# cherrymx1.net
KiCad netlist of a schematic drawn in EAGLE
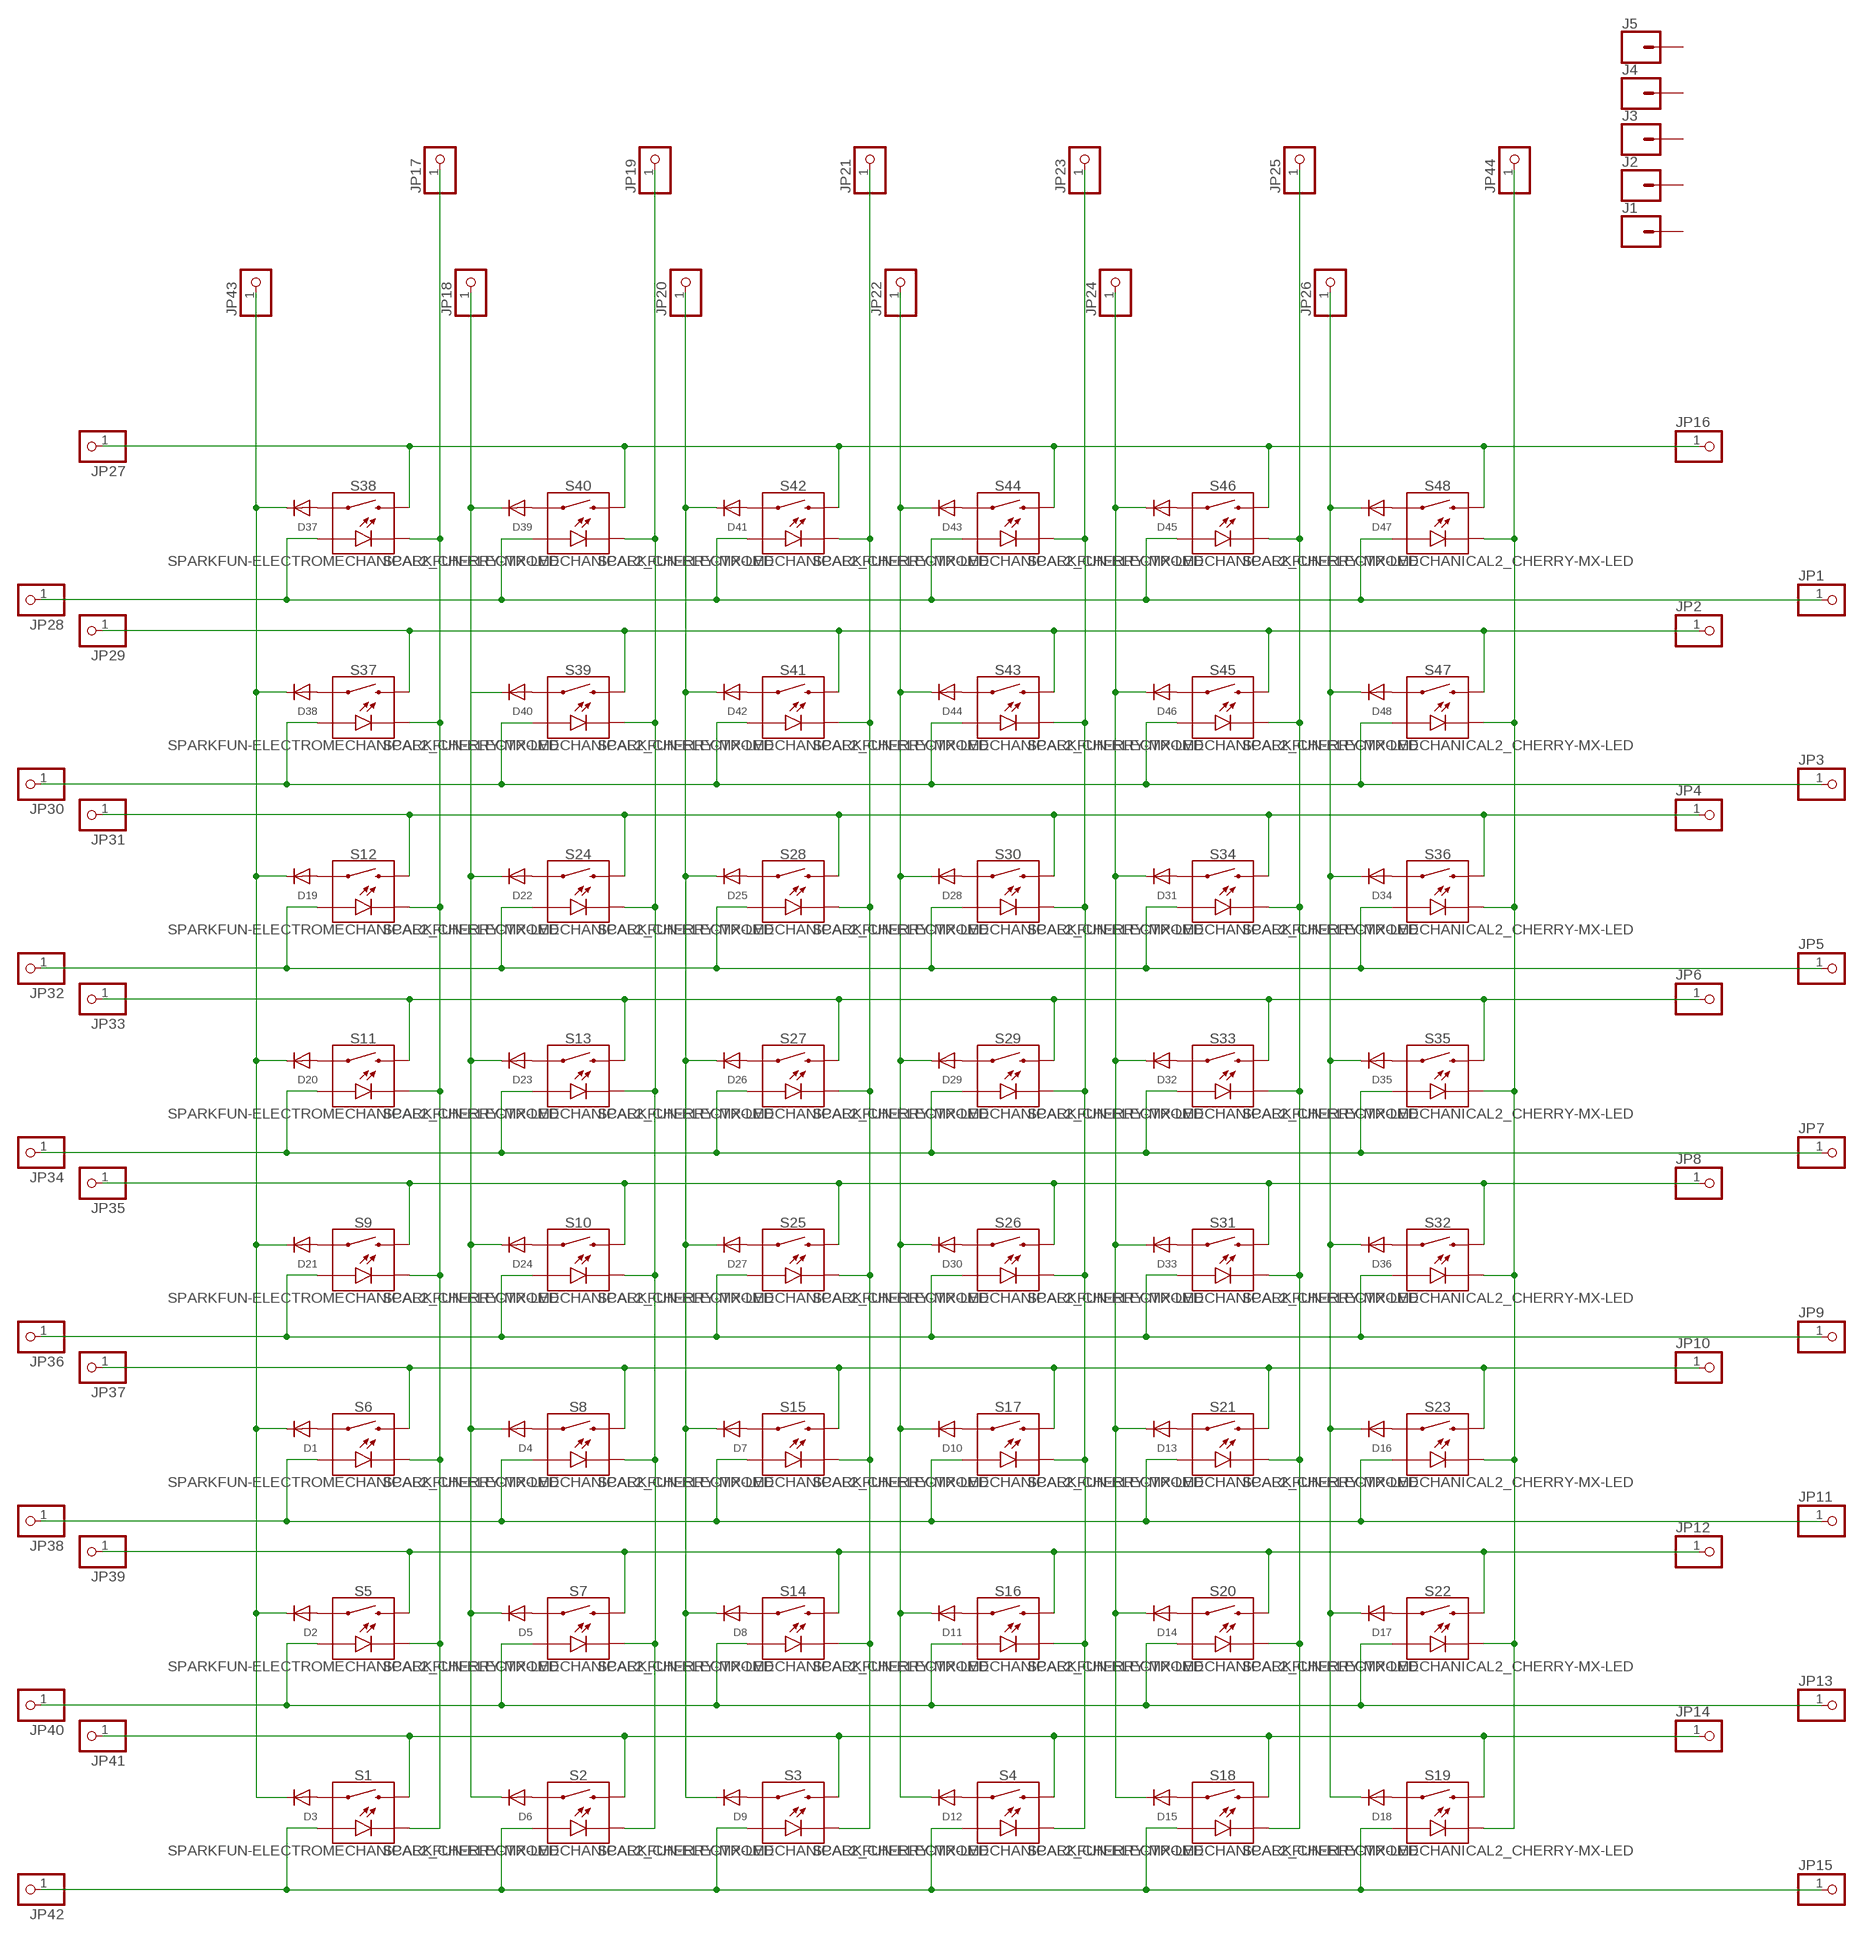
[diagram p0: schematic, sheet 1]

(export (version "E")
  (design (tool "Eeschema 10.0.6"))
  (components
    (comp (ref "D1")
      (value "DIODE_SOD-123FL")
      (footprint "eagle-import:SOD-123FL")
      (libsource (lib "eagle-import") (part "DIODE_SOD-123FL"))
    )
    (comp (ref "D2")
      (value "DIODE_SOD-123FL")
      (footprint "eagle-import:SOD-123FL")
      (libsource (lib "eagle-import") (part "DIODE_SOD-123FL"))
    )
    (comp (ref "D3")
      (value "DIODE_SOD-123FL")
      (footprint "eagle-import:SOD-123FL")
      (libsource (lib "eagle-import") (part "DIODE_SOD-123FL"))
    )
    (comp (ref "D4")
      (value "DIODE_SOD-123FL")
      (footprint "eagle-import:SOD-123FL")
      (libsource (lib "eagle-import") (part "DIODE_SOD-123FL"))
    )
    (comp (ref "D5")
      (value "DIODE_SOD-123FL")
      (footprint "eagle-import:SOD-123FL")
      (libsource (lib "eagle-import") (part "DIODE_SOD-123FL"))
    )
    (comp (ref "D6")
      (value "DIODE_SOD-123FL")
      (footprint "eagle-import:SOD-123FL")
      (libsource (lib "eagle-import") (part "DIODE_SOD-123FL"))
    )
    (comp (ref "D7")
      (value "DIODE_SOD-123FL")
      (footprint "eagle-import:SOD-123FL")
      (libsource (lib "eagle-import") (part "DIODE_SOD-123FL"))
    )
    (comp (ref "D8")
      (value "DIODE_SOD-123FL")
      (footprint "eagle-import:SOD-123FL")
      (libsource (lib "eagle-import") (part "DIODE_SOD-123FL"))
    )
    (comp (ref "D9")
      (value "DIODE_SOD-123FL")
      (footprint "eagle-import:SOD-123FL")
      (libsource (lib "eagle-import") (part "DIODE_SOD-123FL"))
    )
    (comp (ref "D10")
      (value "DIODE_SOD-123FL")
      (footprint "eagle-import:SOD-123FL")
      (libsource (lib "eagle-import") (part "DIODE_SOD-123FL"))
    )
    (comp (ref "D11")
      (value "DIODE_SOD-123FL")
      (footprint "eagle-import:SOD-123FL")
      (libsource (lib "eagle-import") (part "DIODE_SOD-123FL"))
    )
    (comp (ref "D12")
      (value "DIODE_SOD-123FL")
      (footprint "eagle-import:SOD-123FL")
      (libsource (lib "eagle-import") (part "DIODE_SOD-123FL"))
    )
    (comp (ref "D13")
      (value "DIODE_SOD-123FL")
      (footprint "eagle-import:SOD-123FL")
      (libsource (lib "eagle-import") (part "DIODE_SOD-123FL"))
    )
    (comp (ref "D14")
      (value "DIODE_SOD-123FL")
      (footprint "eagle-import:SOD-123FL")
      (libsource (lib "eagle-import") (part "DIODE_SOD-123FL"))
    )
    (comp (ref "D15")
      (value "DIODE_SOD-123FL")
      (footprint "eagle-import:SOD-123FL")
      (libsource (lib "eagle-import") (part "DIODE_SOD-123FL"))
    )
    (comp (ref "D16")
      (value "DIODE_SOD-123FL")
      (footprint "eagle-import:SOD-123FL")
      (libsource (lib "eagle-import") (part "DIODE_SOD-123FL"))
    )
    (comp (ref "D17")
      (value "DIODE_SOD-123FL")
      (footprint "eagle-import:SOD-123FL")
      (libsource (lib "eagle-import") (part "DIODE_SOD-123FL"))
    )
    (comp (ref "D18")
      (value "DIODE_SOD-123FL")
      (footprint "eagle-import:SOD-123FL")
      (libsource (lib "eagle-import") (part "DIODE_SOD-123FL"))
    )
    (comp (ref "D19")
      (value "DIODE_SOD-123FL")
      (footprint "eagle-import:SOD-123FL")
      (libsource (lib "eagle-import") (part "DIODE_SOD-123FL"))
    )
    (comp (ref "D20")
      (value "DIODE_SOD-123FL")
      (footprint "eagle-import:SOD-123FL")
      (libsource (lib "eagle-import") (part "DIODE_SOD-123FL"))
    )
    (comp (ref "D21")
      (value "DIODE_SOD-123FL")
      (footprint "eagle-import:SOD-123FL")
      (libsource (lib "eagle-import") (part "DIODE_SOD-123FL"))
    )
    (comp (ref "D22")
      (value "DIODE_SOD-123FL")
      (footprint "eagle-import:SOD-123FL")
      (libsource (lib "eagle-import") (part "DIODE_SOD-123FL"))
    )
    (comp (ref "D23")
      (value "DIODE_SOD-123FL")
      (footprint "eagle-import:SOD-123FL")
      (libsource (lib "eagle-import") (part "DIODE_SOD-123FL"))
    )
    (comp (ref "D24")
      (value "DIODE_SOD-123FL")
      (footprint "eagle-import:SOD-123FL")
      (libsource (lib "eagle-import") (part "DIODE_SOD-123FL"))
    )
    (comp (ref "D25")
      (value "DIODE_SOD-123FL")
      (footprint "eagle-import:SOD-123FL")
      (libsource (lib "eagle-import") (part "DIODE_SOD-123FL"))
    )
    (comp (ref "D26")
      (value "DIODE_SOD-123FL")
      (footprint "eagle-import:SOD-123FL")
      (libsource (lib "eagle-import") (part "DIODE_SOD-123FL"))
    )
    (comp (ref "D27")
      (value "DIODE_SOD-123FL")
      (footprint "eagle-import:SOD-123FL")
      (libsource (lib "eagle-import") (part "DIODE_SOD-123FL"))
    )
    (comp (ref "D28")
      (value "DIODE_SOD-123FL")
      (footprint "eagle-import:SOD-123FL")
      (libsource (lib "eagle-import") (part "DIODE_SOD-123FL"))
    )
    (comp (ref "D29")
      (value "DIODE_SOD-123FL")
      (footprint "eagle-import:SOD-123FL")
      (libsource (lib "eagle-import") (part "DIODE_SOD-123FL"))
    )
    (comp (ref "D30")
      (value "DIODE_SOD-123FL")
      (footprint "eagle-import:SOD-123FL")
      (libsource (lib "eagle-import") (part "DIODE_SOD-123FL"))
    )
    (comp (ref "D31")
      (value "DIODE_SOD-123FL")
      (footprint "eagle-import:SOD-123FL")
      (libsource (lib "eagle-import") (part "DIODE_SOD-123FL"))
    )
    (comp (ref "D32")
      (value "DIODE_SOD-123FL")
      (footprint "eagle-import:SOD-123FL")
      (libsource (lib "eagle-import") (part "DIODE_SOD-123FL"))
    )
    (comp (ref "D33")
      (value "DIODE_SOD-123FL")
      (footprint "eagle-import:SOD-123FL")
      (libsource (lib "eagle-import") (part "DIODE_SOD-123FL"))
    )
    (comp (ref "D34")
      (value "DIODE_SOD-123FL")
      (footprint "eagle-import:SOD-123FL")
      (libsource (lib "eagle-import") (part "DIODE_SOD-123FL"))
    )
    (comp (ref "D35")
      (value "DIODE_SOD-123FL")
      (footprint "eagle-import:SOD-123FL")
      (libsource (lib "eagle-import") (part "DIODE_SOD-123FL"))
    )
    (comp (ref "D36")
      (value "DIODE_SOD-123FL")
      (footprint "eagle-import:SOD-123FL")
      (libsource (lib "eagle-import") (part "DIODE_SOD-123FL"))
    )
    (comp (ref "D37")
      (value "DIODE_SOD-123FL")
      (footprint "eagle-import:SOD-123FL")
      (libsource (lib "eagle-import") (part "DIODE_SOD-123FL"))
    )
    (comp (ref "D38")
      (value "DIODE_SOD-123FL")
      (footprint "eagle-import:SOD-123FL")
      (libsource (lib "eagle-import") (part "DIODE_SOD-123FL"))
    )
    (comp (ref "D39")
      (value "DIODE_SOD-123FL")
      (footprint "eagle-import:SOD-123FL")
      (libsource (lib "eagle-import") (part "DIODE_SOD-123FL"))
    )
    (comp (ref "D40")
      (value "DIODE_SOD-123FL")
      (footprint "eagle-import:SOD-123FL")
      (libsource (lib "eagle-import") (part "DIODE_SOD-123FL"))
    )
    (comp (ref "D41")
      (value "DIODE_SOD-123FL")
      (footprint "eagle-import:SOD-123FL")
      (libsource (lib "eagle-import") (part "DIODE_SOD-123FL"))
    )
    (comp (ref "D42")
      (value "DIODE_SOD-123FL")
      (footprint "eagle-import:SOD-123FL")
      (libsource (lib "eagle-import") (part "DIODE_SOD-123FL"))
    )
    (comp (ref "D43")
      (value "DIODE_SOD-123FL")
      (footprint "eagle-import:SOD-123FL")
      (libsource (lib "eagle-import") (part "DIODE_SOD-123FL"))
    )
    (comp (ref "D44")
      (value "DIODE_SOD-123FL")
      (footprint "eagle-import:SOD-123FL")
      (libsource (lib "eagle-import") (part "DIODE_SOD-123FL"))
    )
    (comp (ref "D45")
      (value "DIODE_SOD-123FL")
      (footprint "eagle-import:SOD-123FL")
      (libsource (lib "eagle-import") (part "DIODE_SOD-123FL"))
    )
    (comp (ref "D46")
      (value "DIODE_SOD-123FL")
      (footprint "eagle-import:SOD-123FL")
      (libsource (lib "eagle-import") (part "DIODE_SOD-123FL"))
    )
    (comp (ref "D47")
      (value "DIODE_SOD-123FL")
      (footprint "eagle-import:SOD-123FL")
      (libsource (lib "eagle-import") (part "DIODE_SOD-123FL"))
    )
    (comp (ref "D48")
      (value "DIODE_SOD-123FL")
      (footprint "eagle-import:SOD-123FL")
      (libsource (lib "eagle-import") (part "DIODE_SOD-123FL"))
    )
    (comp (ref "J1")
      (value "CONN_01SMTSO-256-ET-0.165DIA")
      (footprint "eagle-import:SMTSO-256-ET-0.165DIA")
      (libsource (lib "eagle-import") (part "CONN_01SMTSO-256-ET-0.165DIA"))
    )
    (comp (ref "J2")
      (value "CONN_01SMTSO-256-ET-0.165DIA")
      (footprint "eagle-import:SMTSO-256-ET-0.165DIA")
      (libsource (lib "eagle-import") (part "CONN_01SMTSO-256-ET-0.165DIA"))
    )
    (comp (ref "J3")
      (value "CONN_01SMTSO-256-ET-0.165DIA")
      (footprint "eagle-import:SMTSO-256-ET-0.165DIA")
      (libsource (lib "eagle-import") (part "CONN_01SMTSO-256-ET-0.165DIA"))
    )
    (comp (ref "J4")
      (value "CONN_01SMTSO-256-ET-0.165DIA")
      (footprint "eagle-import:SMTSO-256-ET-0.165DIA")
      (libsource (lib "eagle-import") (part "CONN_01SMTSO-256-ET-0.165DIA"))
    )
    (comp (ref "J5")
      (value "CONN_01SMTSO-256-ET-0.165DIA")
      (footprint "eagle-import:SMTSO-256-ET-0.165DIA")
      (libsource (lib "eagle-import") (part "CONN_01SMTSO-256-ET-0.165DIA"))
    )
    (comp (ref "JP1")
      (value "MICROBUILDER_HEADER-1X51X1_EDGESMT")
      (footprint "eagle-import:MICROBUILDER_1X5_SMT")
      (libsource (lib "eagle-import") (part "MICROBUILDER_HEADER-1X51X1_EDGESMT"))
    )
    (comp (ref "JP2")
      (value "MICROBUILDER_HEADER-1X51X1_EDGESMT")
      (footprint "eagle-import:MICROBUILDER_1X5_SMT")
      (libsource (lib "eagle-import") (part "MICROBUILDER_HEADER-1X51X1_EDGESMT"))
    )
    (comp (ref "JP3")
      (value "MICROBUILDER_HEADER-1X51X1_EDGESMT")
      (footprint "eagle-import:MICROBUILDER_1X5_SMT")
      (libsource (lib "eagle-import") (part "MICROBUILDER_HEADER-1X51X1_EDGESMT"))
    )
    (comp (ref "JP4")
      (value "MICROBUILDER_HEADER-1X51X1_EDGESMT")
      (footprint "eagle-import:MICROBUILDER_1X5_SMT")
      (libsource (lib "eagle-import") (part "MICROBUILDER_HEADER-1X51X1_EDGESMT"))
    )
    (comp (ref "JP5")
      (value "MICROBUILDER_HEADER-1X51X1_EDGESMT")
      (footprint "eagle-import:MICROBUILDER_1X5_SMT")
      (libsource (lib "eagle-import") (part "MICROBUILDER_HEADER-1X51X1_EDGESMT"))
    )
    (comp (ref "JP6")
      (value "MICROBUILDER_HEADER-1X51X1_EDGESMT")
      (footprint "eagle-import:MICROBUILDER_1X5_SMT")
      (libsource (lib "eagle-import") (part "MICROBUILDER_HEADER-1X51X1_EDGESMT"))
    )
    (comp (ref "JP7")
      (value "MICROBUILDER_HEADER-1X51X1_EDGESMT")
      (footprint "eagle-import:MICROBUILDER_1X5_SMT")
      (libsource (lib "eagle-import") (part "MICROBUILDER_HEADER-1X51X1_EDGESMT"))
    )
    (comp (ref "JP8")
      (value "MICROBUILDER_HEADER-1X51X1_EDGESMT")
      (footprint "eagle-import:MICROBUILDER_1X5_SMT")
      (libsource (lib "eagle-import") (part "MICROBUILDER_HEADER-1X51X1_EDGESMT"))
    )
    (comp (ref "JP9")
      (value "MICROBUILDER_HEADER-1X51X1_EDGESMT")
      (footprint "eagle-import:MICROBUILDER_1X5_SMT")
      (libsource (lib "eagle-import") (part "MICROBUILDER_HEADER-1X51X1_EDGESMT"))
    )
    (comp (ref "JP10")
      (value "MICROBUILDER_HEADER-1X51X1_EDGESMT")
      (footprint "eagle-import:MICROBUILDER_1X5_SMT")
      (libsource (lib "eagle-import") (part "MICROBUILDER_HEADER-1X51X1_EDGESMT"))
    )
    (comp (ref "JP11")
      (value "MICROBUILDER_HEADER-1X51X1_EDGESMT")
      (footprint "eagle-import:MICROBUILDER_1X5_SMT")
      (libsource (lib "eagle-import") (part "MICROBUILDER_HEADER-1X51X1_EDGESMT"))
    )
    (comp (ref "JP12")
      (value "MICROBUILDER_HEADER-1X51X1_EDGESMT")
      (footprint "eagle-import:MICROBUILDER_1X5_SMT")
      (libsource (lib "eagle-import") (part "MICROBUILDER_HEADER-1X51X1_EDGESMT"))
    )
    (comp (ref "JP13")
      (value "MICROBUILDER_HEADER-1X51X1_EDGESMT")
      (footprint "eagle-import:MICROBUILDER_1X5_SMT")
      (libsource (lib "eagle-import") (part "MICROBUILDER_HEADER-1X51X1_EDGESMT"))
    )
    (comp (ref "JP14")
      (value "MICROBUILDER_HEADER-1X51X1_EDGESMT")
      (footprint "eagle-import:MICROBUILDER_1X5_SMT")
      (libsource (lib "eagle-import") (part "MICROBUILDER_HEADER-1X51X1_EDGESMT"))
    )
    (comp (ref "JP15")
      (value "MICROBUILDER_HEADER-1X51X1_EDGESMT")
      (footprint "eagle-import:MICROBUILDER_1X5_SMT")
      (libsource (lib "eagle-import") (part "MICROBUILDER_HEADER-1X51X1_EDGESMT"))
    )
    (comp (ref "JP16")
      (value "MICROBUILDER_HEADER-1X51X1_EDGESMT")
      (footprint "eagle-import:MICROBUILDER_1X5_SMT")
      (libsource (lib "eagle-import") (part "MICROBUILDER_HEADER-1X51X1_EDGESMT"))
    )
    (comp (ref "JP17")
      (value "MICROBUILDER_HEADER-1X51X1_EDGESMT")
      (footprint "eagle-import:MICROBUILDER_1X5_SMT")
      (libsource (lib "eagle-import") (part "MICROBUILDER_HEADER-1X51X1_EDGESMT"))
    )
    (comp (ref "JP18")
      (value "MICROBUILDER_HEADER-1X51X1_EDGESMT")
      (footprint "eagle-import:MICROBUILDER_1X5_SMT")
      (libsource (lib "eagle-import") (part "MICROBUILDER_HEADER-1X51X1_EDGESMT"))
    )
    (comp (ref "JP19")
      (value "MICROBUILDER_HEADER-1X51X1_EDGESMT")
      (footprint "eagle-import:MICROBUILDER_1X5_SMT")
      (libsource (lib "eagle-import") (part "MICROBUILDER_HEADER-1X51X1_EDGESMT"))
    )
    (comp (ref "JP20")
      (value "MICROBUILDER_HEADER-1X51X1_EDGESMT")
      (footprint "eagle-import:MICROBUILDER_1X5_SMT")
      (libsource (lib "eagle-import") (part "MICROBUILDER_HEADER-1X51X1_EDGESMT"))
    )
    (comp (ref "JP21")
      (value "MICROBUILDER_HEADER-1X51X1_EDGESMT")
      (footprint "eagle-import:MICROBUILDER_1X5_SMT")
      (libsource (lib "eagle-import") (part "MICROBUILDER_HEADER-1X51X1_EDGESMT"))
    )
    (comp (ref "JP22")
      (value "MICROBUILDER_HEADER-1X51X1_EDGESMT")
      (footprint "eagle-import:MICROBUILDER_1X5_SMT")
      (libsource (lib "eagle-import") (part "MICROBUILDER_HEADER-1X51X1_EDGESMT"))
    )
    (comp (ref "JP23")
      (value "MICROBUILDER_HEADER-1X51X1_EDGESMT")
      (footprint "eagle-import:MICROBUILDER_1X5_SMT")
      (libsource (lib "eagle-import") (part "MICROBUILDER_HEADER-1X51X1_EDGESMT"))
    )
    (comp (ref "JP24")
      (value "MICROBUILDER_HEADER-1X51X1_EDGESMT")
      (footprint "eagle-import:MICROBUILDER_1X5_SMT")
      (libsource (lib "eagle-import") (part "MICROBUILDER_HEADER-1X51X1_EDGESMT"))
    )
    (comp (ref "JP25")
      (value "MICROBUILDER_HEADER-1X51X1_EDGESMT")
      (footprint "eagle-import:MICROBUILDER_1X5_SMT")
      (libsource (lib "eagle-import") (part "MICROBUILDER_HEADER-1X51X1_EDGESMT"))
    )
    (comp (ref "JP26")
      (value "MICROBUILDER_HEADER-1X51X1_EDGESMT")
      (footprint "eagle-import:MICROBUILDER_1X5_SMT")
      (libsource (lib "eagle-import") (part "MICROBUILDER_HEADER-1X51X1_EDGESMT"))
    )
    (comp (ref "JP27")
      (value "MICROBUILDER_HEADER-1X51X1_EDGESMT")
      (footprint "eagle-import:MICROBUILDER_1X5_SMT")
      (libsource (lib "eagle-import") (part "MICROBUILDER_HEADER-1X51X1_EDGESMT"))
    )
    (comp (ref "JP28")
      (value "MICROBUILDER_HEADER-1X51X1_EDGESMT")
      (footprint "eagle-import:MICROBUILDER_1X5_SMT")
      (libsource (lib "eagle-import") (part "MICROBUILDER_HEADER-1X51X1_EDGESMT"))
    )
    (comp (ref "JP29")
      (value "MICROBUILDER_HEADER-1X51X1_EDGESMT")
      (footprint "eagle-import:MICROBUILDER_1X5_SMT")
      (libsource (lib "eagle-import") (part "MICROBUILDER_HEADER-1X51X1_EDGESMT"))
    )
    (comp (ref "JP30")
      (value "MICROBUILDER_HEADER-1X51X1_EDGESMT")
      (footprint "eagle-import:MICROBUILDER_1X5_SMT")
      (libsource (lib "eagle-import") (part "MICROBUILDER_HEADER-1X51X1_EDGESMT"))
    )
    (comp (ref "JP31")
      (value "MICROBUILDER_HEADER-1X51X1_EDGESMT")
      (footprint "eagle-import:MICROBUILDER_1X5_SMT")
      (libsource (lib "eagle-import") (part "MICROBUILDER_HEADER-1X51X1_EDGESMT"))
    )
    (comp (ref "JP32")
      (value "MICROBUILDER_HEADER-1X51X1_EDGESMT")
      (footprint "eagle-import:MICROBUILDER_1X5_SMT")
      (libsource (lib "eagle-import") (part "MICROBUILDER_HEADER-1X51X1_EDGESMT"))
    )
    (comp (ref "JP33")
      (value "MICROBUILDER_HEADER-1X51X1_EDGESMT")
      (footprint "eagle-import:MICROBUILDER_1X5_SMT")
      (libsource (lib "eagle-import") (part "MICROBUILDER_HEADER-1X51X1_EDGESMT"))
    )
    (comp (ref "JP34")
      (value "MICROBUILDER_HEADER-1X51X1_EDGESMT")
      (footprint "eagle-import:MICROBUILDER_1X5_SMT")
      (libsource (lib "eagle-import") (part "MICROBUILDER_HEADER-1X51X1_EDGESMT"))
    )
    (comp (ref "JP35")
      (value "MICROBUILDER_HEADER-1X51X1_EDGESMT")
      (footprint "eagle-import:MICROBUILDER_1X5_SMT")
      (libsource (lib "eagle-import") (part "MICROBUILDER_HEADER-1X51X1_EDGESMT"))
    )
    (comp (ref "JP36")
      (value "MICROBUILDER_HEADER-1X51X1_EDGESMT")
      (footprint "eagle-import:MICROBUILDER_1X5_SMT")
      (libsource (lib "eagle-import") (part "MICROBUILDER_HEADER-1X51X1_EDGESMT"))
    )
    (comp (ref "JP37")
      (value "MICROBUILDER_HEADER-1X51X1_EDGESMT")
      (footprint "eagle-import:MICROBUILDER_1X5_SMT")
      (libsource (lib "eagle-import") (part "MICROBUILDER_HEADER-1X51X1_EDGESMT"))
    )
    (comp (ref "JP38")
      (value "MICROBUILDER_HEADER-1X51X1_EDGESMT")
      (footprint "eagle-import:MICROBUILDER_1X5_SMT")
      (libsource (lib "eagle-import") (part "MICROBUILDER_HEADER-1X51X1_EDGESMT"))
    )
    (comp (ref "JP39")
      (value "MICROBUILDER_HEADER-1X51X1_EDGESMT")
      (footprint "eagle-import:MICROBUILDER_1X5_SMT")
      (libsource (lib "eagle-import") (part "MICROBUILDER_HEADER-1X51X1_EDGESMT"))
    )
    (comp (ref "JP40")
      (value "MICROBUILDER_HEADER-1X51X1_EDGESMT")
      (footprint "eagle-import:MICROBUILDER_1X5_SMT")
      (libsource (lib "eagle-import") (part "MICROBUILDER_HEADER-1X51X1_EDGESMT"))
    )
    (comp (ref "JP41")
      (value "MICROBUILDER_HEADER-1X51X1_EDGESMT")
      (footprint "eagle-import:MICROBUILDER_1X5_SMT")
      (libsource (lib "eagle-import") (part "MICROBUILDER_HEADER-1X51X1_EDGESMT"))
    )
    (comp (ref "JP42")
      (value "MICROBUILDER_HEADER-1X51X1_EDGESMT")
      (footprint "eagle-import:MICROBUILDER_1X5_SMT")
      (libsource (lib "eagle-import") (part "MICROBUILDER_HEADER-1X51X1_EDGESMT"))
    )
    (comp (ref "JP43")
      (value "MICROBUILDER_HEADER-1X51X1_EDGESMT")
      (footprint "eagle-import:MICROBUILDER_1X5_SMT")
      (libsource (lib "eagle-import") (part "MICROBUILDER_HEADER-1X51X1_EDGESMT"))
    )
    (comp (ref "JP44")
      (value "MICROBUILDER_HEADER-1X51X1_EDGESMT")
      (footprint "eagle-import:MICROBUILDER_1X5_SMT")
      (libsource (lib "eagle-import") (part "MICROBUILDER_HEADER-1X51X1_EDGESMT"))
    )
    (comp (ref "S1")
      (value "SPARKFUN-ELECTROMECHANICAL2_CHERRY-MX-LED")
      (footprint "eagle-import:SPARKFUN-ELECTROMECHANICAL2_CHERRY-MX-LED")
      (libsource (lib "eagle-import") (part "SPARKFUN-ELECTROMECHANICAL2_CHERRY-MX-LED"))
    )
    (comp (ref "S2")
      (value "SPARKFUN-ELECTROMECHANICAL2_CHERRY-MX-LED")
      (footprint "eagle-import:SPARKFUN-ELECTROMECHANICAL2_CHERRY-MX-LED")
      (libsource (lib "eagle-import") (part "SPARKFUN-ELECTROMECHANICAL2_CHERRY-MX-LED"))
    )
    (comp (ref "S3")
      (value "SPARKFUN-ELECTROMECHANICAL2_CHERRY-MX-LED")
      (footprint "eagle-import:SPARKFUN-ELECTROMECHANICAL2_CHERRY-MX-LED")
      (libsource (lib "eagle-import") (part "SPARKFUN-ELECTROMECHANICAL2_CHERRY-MX-LED"))
    )
    (comp (ref "S4")
      (value "SPARKFUN-ELECTROMECHANICAL2_CHERRY-MX-LED")
      (footprint "eagle-import:SPARKFUN-ELECTROMECHANICAL2_CHERRY-MX-LED")
      (libsource (lib "eagle-import") (part "SPARKFUN-ELECTROMECHANICAL2_CHERRY-MX-LED"))
    )
    (comp (ref "S5")
      (value "SPARKFUN-ELECTROMECHANICAL2_CHERRY-MX-LED")
      (footprint "eagle-import:SPARKFUN-ELECTROMECHANICAL2_CHERRY-MX-LED")
      (libsource (lib "eagle-import") (part "SPARKFUN-ELECTROMECHANICAL2_CHERRY-MX-LED"))
    )
    (comp (ref "S6")
      (value "SPARKFUN-ELECTROMECHANICAL2_CHERRY-MX-LED")
      (footprint "eagle-import:SPARKFUN-ELECTROMECHANICAL2_CHERRY-MX-LED")
      (libsource (lib "eagle-import") (part "SPARKFUN-ELECTROMECHANICAL2_CHERRY-MX-LED"))
    )
    (comp (ref "S7")
      (value "SPARKFUN-ELECTROMECHANICAL2_CHERRY-MX-LED")
      (footprint "eagle-import:SPARKFUN-ELECTROMECHANICAL2_CHERRY-MX-LED")
      (libsource (lib "eagle-import") (part "SPARKFUN-ELECTROMECHANICAL2_CHERRY-MX-LED"))
    )
    (comp (ref "S8")
      (value "SPARKFUN-ELECTROMECHANICAL2_CHERRY-MX-LED")
      (footprint "eagle-import:SPARKFUN-ELECTROMECHANICAL2_CHERRY-MX-LED")
      (libsource (lib "eagle-import") (part "SPARKFUN-ELECTROMECHANICAL2_CHERRY-MX-LED"))
    )
    (comp (ref "S9")
      (value "SPARKFUN-ELECTROMECHANICAL2_CHERRY-MX-LED")
      (footprint "eagle-import:SPARKFUN-ELECTROMECHANICAL2_CHERRY-MX-LED")
      (libsource (lib "eagle-import") (part "SPARKFUN-ELECTROMECHANICAL2_CHERRY-MX-LED"))
    )
    (comp (ref "S10")
      (value "SPARKFUN-ELECTROMECHANICAL2_CHERRY-MX-LED")
      (footprint "eagle-import:SPARKFUN-ELECTROMECHANICAL2_CHERRY-MX-LED")
      (libsource (lib "eagle-import") (part "SPARKFUN-ELECTROMECHANICAL2_CHERRY-MX-LED"))
    )
    (comp (ref "S11")
      (value "SPARKFUN-ELECTROMECHANICAL2_CHERRY-MX-LED")
      (footprint "eagle-import:SPARKFUN-ELECTROMECHANICAL2_CHERRY-MX-LED")
      (libsource (lib "eagle-import") (part "SPARKFUN-ELECTROMECHANICAL2_CHERRY-MX-LED"))
    )
    (comp (ref "S12")
      (value "SPARKFUN-ELECTROMECHANICAL2_CHERRY-MX-LED")
      (footprint "eagle-import:SPARKFUN-ELECTROMECHANICAL2_CHERRY-MX-LED")
      (libsource (lib "eagle-import") (part "SPARKFUN-ELECTROMECHANICAL2_CHERRY-MX-LED"))
    )
    (comp (ref "S13")
      (value "SPARKFUN-ELECTROMECHANICAL2_CHERRY-MX-LED")
      (footprint "eagle-import:SPARKFUN-ELECTROMECHANICAL2_CHERRY-MX-LED")
      (libsource (lib "eagle-import") (part "SPARKFUN-ELECTROMECHANICAL2_CHERRY-MX-LED"))
    )
    (comp (ref "S14")
      (value "SPARKFUN-ELECTROMECHANICAL2_CHERRY-MX-LED")
      (footprint "eagle-import:SPARKFUN-ELECTROMECHANICAL2_CHERRY-MX-LED")
      (libsource (lib "eagle-import") (part "SPARKFUN-ELECTROMECHANICAL2_CHERRY-MX-LED"))
    )
    (comp (ref "S15")
      (value "SPARKFUN-ELECTROMECHANICAL2_CHERRY-MX-LED")
      (footprint "eagle-import:SPARKFUN-ELECTROMECHANICAL2_CHERRY-MX-LED")
      (libsource (lib "eagle-import") (part "SPARKFUN-ELECTROMECHANICAL2_CHERRY-MX-LED"))
    )
    (comp (ref "S16")
      (value "SPARKFUN-ELECTROMECHANICAL2_CHERRY-MX-LED")
      (footprint "eagle-import:SPARKFUN-ELECTROMECHANICAL2_CHERRY-MX-LED")
      (libsource (lib "eagle-import") (part "SPARKFUN-ELECTROMECHANICAL2_CHERRY-MX-LED"))
    )
    (comp (ref "S17")
      (value "SPARKFUN-ELECTROMECHANICAL2_CHERRY-MX-LED")
      (footprint "eagle-import:SPARKFUN-ELECTROMECHANICAL2_CHERRY-MX-LED")
      (libsource (lib "eagle-import") (part "SPARKFUN-ELECTROMECHANICAL2_CHERRY-MX-LED"))
    )
    (comp (ref "S18")
      (value "SPARKFUN-ELECTROMECHANICAL2_CHERRY-MX-LED")
      (footprint "eagle-import:SPARKFUN-ELECTROMECHANICAL2_CHERRY-MX-LED")
      (libsource (lib "eagle-import") (part "SPARKFUN-ELECTROMECHANICAL2_CHERRY-MX-LED"))
    )
    (comp (ref "S19")
      (value "SPARKFUN-ELECTROMECHANICAL2_CHERRY-MX-LED")
      (footprint "eagle-import:SPARKFUN-ELECTROMECHANICAL2_CHERRY-MX-LED")
      (libsource (lib "eagle-import") (part "SPARKFUN-ELECTROMECHANICAL2_CHERRY-MX-LED"))
    )
    (comp (ref "S20")
      (value "SPARKFUN-ELECTROMECHANICAL2_CHERRY-MX-LED")
      (footprint "eagle-import:SPARKFUN-ELECTROMECHANICAL2_CHERRY-MX-LED")
      (libsource (lib "eagle-import") (part "SPARKFUN-ELECTROMECHANICAL2_CHERRY-MX-LED"))
    )
    (comp (ref "S21")
      (value "SPARKFUN-ELECTROMECHANICAL2_CHERRY-MX-LED")
      (footprint "eagle-import:SPARKFUN-ELECTROMECHANICAL2_CHERRY-MX-LED")
      (libsource (lib "eagle-import") (part "SPARKFUN-ELECTROMECHANICAL2_CHERRY-MX-LED"))
    )
    (comp (ref "S22")
      (value "SPARKFUN-ELECTROMECHANICAL2_CHERRY-MX-LED")
      (footprint "eagle-import:SPARKFUN-ELECTROMECHANICAL2_CHERRY-MX-LED")
      (libsource (lib "eagle-import") (part "SPARKFUN-ELECTROMECHANICAL2_CHERRY-MX-LED"))
    )
    (comp (ref "S23")
      (value "SPARKFUN-ELECTROMECHANICAL2_CHERRY-MX-LED")
      (footprint "eagle-import:SPARKFUN-ELECTROMECHANICAL2_CHERRY-MX-LED")
      (libsource (lib "eagle-import") (part "SPARKFUN-ELECTROMECHANICAL2_CHERRY-MX-LED"))
    )
    (comp (ref "S24")
      (value "SPARKFUN-ELECTROMECHANICAL2_CHERRY-MX-LED")
      (footprint "eagle-import:SPARKFUN-ELECTROMECHANICAL2_CHERRY-MX-LED")
      (libsource (lib "eagle-import") (part "SPARKFUN-ELECTROMECHANICAL2_CHERRY-MX-LED"))
    )
    (comp (ref "S25")
      (value "SPARKFUN-ELECTROMECHANICAL2_CHERRY-MX-LED")
      (footprint "eagle-import:SPARKFUN-ELECTROMECHANICAL2_CHERRY-MX-LED")
      (libsource (lib "eagle-import") (part "SPARKFUN-ELECTROMECHANICAL2_CHERRY-MX-LED"))
    )
    (comp (ref "S26")
      (value "SPARKFUN-ELECTROMECHANICAL2_CHERRY-MX-LED")
      (footprint "eagle-import:SPARKFUN-ELECTROMECHANICAL2_CHERRY-MX-LED")
      (libsource (lib "eagle-import") (part "SPARKFUN-ELECTROMECHANICAL2_CHERRY-MX-LED"))
    )
    (comp (ref "S27")
      (value "SPARKFUN-ELECTROMECHANICAL2_CHERRY-MX-LED")
      (footprint "eagle-import:SPARKFUN-ELECTROMECHANICAL2_CHERRY-MX-LED")
      (libsource (lib "eagle-import") (part "SPARKFUN-ELECTROMECHANICAL2_CHERRY-MX-LED"))
    )
    (comp (ref "S28")
      (value "SPARKFUN-ELECTROMECHANICAL2_CHERRY-MX-LED")
      (footprint "eagle-import:SPARKFUN-ELECTROMECHANICAL2_CHERRY-MX-LED")
      (libsource (lib "eagle-import") (part "SPARKFUN-ELECTROMECHANICAL2_CHERRY-MX-LED"))
    )
    (comp (ref "S29")
      (value "SPARKFUN-ELECTROMECHANICAL2_CHERRY-MX-LED")
      (footprint "eagle-import:SPARKFUN-ELECTROMECHANICAL2_CHERRY-MX-LED")
      (libsource (lib "eagle-import") (part "SPARKFUN-ELECTROMECHANICAL2_CHERRY-MX-LED"))
    )
    (comp (ref "S30")
      (value "SPARKFUN-ELECTROMECHANICAL2_CHERRY-MX-LED")
      (footprint "eagle-import:SPARKFUN-ELECTROMECHANICAL2_CHERRY-MX-LED")
      (libsource (lib "eagle-import") (part "SPARKFUN-ELECTROMECHANICAL2_CHERRY-MX-LED"))
    )
    (comp (ref "S31")
      (value "SPARKFUN-ELECTROMECHANICAL2_CHERRY-MX-LED")
      (footprint "eagle-import:SPARKFUN-ELECTROMECHANICAL2_CHERRY-MX-LED")
      (libsource (lib "eagle-import") (part "SPARKFUN-ELECTROMECHANICAL2_CHERRY-MX-LED"))
    )
    (comp (ref "S32")
      (value "SPARKFUN-ELECTROMECHANICAL2_CHERRY-MX-LED")
      (footprint "eagle-import:SPARKFUN-ELECTROMECHANICAL2_CHERRY-MX-LED")
      (libsource (lib "eagle-import") (part "SPARKFUN-ELECTROMECHANICAL2_CHERRY-MX-LED"))
    )
    (comp (ref "S33")
      (value "SPARKFUN-ELECTROMECHANICAL2_CHERRY-MX-LED")
      (footprint "eagle-import:SPARKFUN-ELECTROMECHANICAL2_CHERRY-MX-LED")
      (libsource (lib "eagle-import") (part "SPARKFUN-ELECTROMECHANICAL2_CHERRY-MX-LED"))
    )
    (comp (ref "S34")
      (value "SPARKFUN-ELECTROMECHANICAL2_CHERRY-MX-LED")
      (footprint "eagle-import:SPARKFUN-ELECTROMECHANICAL2_CHERRY-MX-LED")
      (libsource (lib "eagle-import") (part "SPARKFUN-ELECTROMECHANICAL2_CHERRY-MX-LED"))
    )
    (comp (ref "S35")
      (value "SPARKFUN-ELECTROMECHANICAL2_CHERRY-MX-LED")
      (footprint "eagle-import:SPARKFUN-ELECTROMECHANICAL2_CHERRY-MX-LED")
      (libsource (lib "eagle-import") (part "SPARKFUN-ELECTROMECHANICAL2_CHERRY-MX-LED"))
    )
    (comp (ref "S36")
      (value "SPARKFUN-ELECTROMECHANICAL2_CHERRY-MX-LED")
      (footprint "eagle-import:SPARKFUN-ELECTROMECHANICAL2_CHERRY-MX-LED")
      (libsource (lib "eagle-import") (part "SPARKFUN-ELECTROMECHANICAL2_CHERRY-MX-LED"))
    )
    (comp (ref "S37")
      (value "SPARKFUN-ELECTROMECHANICAL2_CHERRY-MX-LED")
      (footprint "eagle-import:SPARKFUN-ELECTROMECHANICAL2_CHERRY-MX-LED")
      (libsource (lib "eagle-import") (part "SPARKFUN-ELECTROMECHANICAL2_CHERRY-MX-LED"))
    )
    (comp (ref "S38")
      (value "SPARKFUN-ELECTROMECHANICAL2_CHERRY-MX-LED")
      (footprint "eagle-import:SPARKFUN-ELECTROMECHANICAL2_CHERRY-MX-LED")
      (libsource (lib "eagle-import") (part "SPARKFUN-ELECTROMECHANICAL2_CHERRY-MX-LED"))
    )
    (comp (ref "S39")
      (value "SPARKFUN-ELECTROMECHANICAL2_CHERRY-MX-LED")
      (footprint "eagle-import:SPARKFUN-ELECTROMECHANICAL2_CHERRY-MX-LED")
      (libsource (lib "eagle-import") (part "SPARKFUN-ELECTROMECHANICAL2_CHERRY-MX-LED"))
    )
    (comp (ref "S40")
      (value "SPARKFUN-ELECTROMECHANICAL2_CHERRY-MX-LED")
      (footprint "eagle-import:SPARKFUN-ELECTROMECHANICAL2_CHERRY-MX-LED")
      (libsource (lib "eagle-import") (part "SPARKFUN-ELECTROMECHANICAL2_CHERRY-MX-LED"))
    )
    (comp (ref "S41")
      (value "SPARKFUN-ELECTROMECHANICAL2_CHERRY-MX-LED")
      (footprint "eagle-import:SPARKFUN-ELECTROMECHANICAL2_CHERRY-MX-LED")
      (libsource (lib "eagle-import") (part "SPARKFUN-ELECTROMECHANICAL2_CHERRY-MX-LED"))
    )
    (comp (ref "S42")
      (value "SPARKFUN-ELECTROMECHANICAL2_CHERRY-MX-LED")
      (footprint "eagle-import:SPARKFUN-ELECTROMECHANICAL2_CHERRY-MX-LED")
      (libsource (lib "eagle-import") (part "SPARKFUN-ELECTROMECHANICAL2_CHERRY-MX-LED"))
    )
    (comp (ref "S43")
      (value "SPARKFUN-ELECTROMECHANICAL2_CHERRY-MX-LED")
      (footprint "eagle-import:SPARKFUN-ELECTROMECHANICAL2_CHERRY-MX-LED")
      (libsource (lib "eagle-import") (part "SPARKFUN-ELECTROMECHANICAL2_CHERRY-MX-LED"))
    )
    (comp (ref "S44")
      (value "SPARKFUN-ELECTROMECHANICAL2_CHERRY-MX-LED")
      (footprint "eagle-import:SPARKFUN-ELECTROMECHANICAL2_CHERRY-MX-LED")
      (libsource (lib "eagle-import") (part "SPARKFUN-ELECTROMECHANICAL2_CHERRY-MX-LED"))
    )
    (comp (ref "S45")
      (value "SPARKFUN-ELECTROMECHANICAL2_CHERRY-MX-LED")
      (footprint "eagle-import:SPARKFUN-ELECTROMECHANICAL2_CHERRY-MX-LED")
      (libsource (lib "eagle-import") (part "SPARKFUN-ELECTROMECHANICAL2_CHERRY-MX-LED"))
    )
    (comp (ref "S46")
      (value "SPARKFUN-ELECTROMECHANICAL2_CHERRY-MX-LED")
      (footprint "eagle-import:SPARKFUN-ELECTROMECHANICAL2_CHERRY-MX-LED")
      (libsource (lib "eagle-import") (part "SPARKFUN-ELECTROMECHANICAL2_CHERRY-MX-LED"))
    )
    (comp (ref "S47")
      (value "SPARKFUN-ELECTROMECHANICAL2_CHERRY-MX-LED")
      (footprint "eagle-import:SPARKFUN-ELECTROMECHANICAL2_CHERRY-MX-LED")
      (libsource (lib "eagle-import") (part "SPARKFUN-ELECTROMECHANICAL2_CHERRY-MX-LED"))
    )
    (comp (ref "S48")
      (value "SPARKFUN-ELECTROMECHANICAL2_CHERRY-MX-LED")
      (footprint "eagle-import:SPARKFUN-ELECTROMECHANICAL2_CHERRY-MX-LED")
      (libsource (lib "eagle-import") (part "SPARKFUN-ELECTROMECHANICAL2_CHERRY-MX-LED"))
    )
  )
  (nets
    (net (code "1") (name "Net-(D1-PadA)") (class "Default")
      (node (ref "D1") (pin "A") (pinfunction "A_A") (pintype "passive"))
      (node (ref "S6") (pin "S1") (pinfunction "S1_S1") (pintype "passive"))
    )
    (net (code "2") (name "Net-(D1-PadC)") (class "Default")
      (node (ref "D1") (pin "C") (pinfunction "C_C") (pintype "passive"))
      (node (ref "D19") (pin "C") (pinfunction "C_C") (pintype "passive"))
      (node (ref "D2") (pin "C") (pinfunction "C_C") (pintype "passive"))
      (node (ref "D20") (pin "C") (pinfunction "C_C") (pintype "passive"))
      (node (ref "D21") (pin "C") (pinfunction "C_C") (pintype "passive"))
      (node (ref "D3") (pin "C") (pinfunction "C_C") (pintype "passive"))
      (node (ref "D37") (pin "C") (pinfunction "C_C") (pintype "passive"))
      (node (ref "D38") (pin "C") (pinfunction "C_C") (pintype "passive"))
      (node (ref "JP43") (pin "1") (pinfunction "1_1") (pintype "passive"))
    )
    (net (code "3") (name "Net-(D2-PadA)") (class "Default")
      (node (ref "D2") (pin "A") (pinfunction "A_A") (pintype "passive"))
      (node (ref "S5") (pin "S1") (pinfunction "S1_S1") (pintype "passive"))
    )
    (net (code "4") (name "Net-(D3-PadA)") (class "Default")
      (node (ref "D3") (pin "A") (pinfunction "A_A") (pintype "passive"))
      (node (ref "S1") (pin "S1") (pinfunction "S1_S1") (pintype "passive"))
    )
    (net (code "5") (name "Net-(D4-PadA)") (class "Default")
      (node (ref "D4") (pin "A") (pinfunction "A_A") (pintype "passive"))
      (node (ref "S8") (pin "S1") (pinfunction "S1_S1") (pintype "passive"))
    )
    (net (code "6") (name "Net-(D5-PadA)") (class "Default")
      (node (ref "D5") (pin "A") (pinfunction "A_A") (pintype "passive"))
      (node (ref "S7") (pin "S1") (pinfunction "S1_S1") (pintype "passive"))
    )
    (net (code "7") (name "Net-(D6-PadA)") (class "Default")
      (node (ref "D6") (pin "A") (pinfunction "A_A") (pintype "passive"))
      (node (ref "S2") (pin "S1") (pinfunction "S1_S1") (pintype "passive"))
    )
    (net (code "8") (name "Net-(D7-PadA)") (class "Default")
      (node (ref "D7") (pin "A") (pinfunction "A_A") (pintype "passive"))
      (node (ref "S15") (pin "S1") (pinfunction "S1_S1") (pintype "passive"))
    )
    (net (code "9") (name "Net-(D8-PadA)") (class "Default")
      (node (ref "D8") (pin "A") (pinfunction "A_A") (pintype "passive"))
      (node (ref "S14") (pin "S1") (pinfunction "S1_S1") (pintype "passive"))
    )
    (net (code "10") (name "Net-(D9-PadA)") (class "Default")
      (node (ref "D9") (pin "A") (pinfunction "A_A") (pintype "passive"))
      (node (ref "S3") (pin "S1") (pinfunction "S1_S1") (pintype "passive"))
    )
    (net (code "11") (name "Net-(D10-PadA)") (class "Default")
      (node (ref "D10") (pin "A") (pinfunction "A_A") (pintype "passive"))
      (node (ref "S17") (pin "S1") (pinfunction "S1_S1") (pintype "passive"))
    )
    (net (code "12") (name "Net-(D10-PadC)") (class "Default")
      (node (ref "D10") (pin "C") (pinfunction "C_C") (pintype "passive"))
      (node (ref "D11") (pin "C") (pinfunction "C_C") (pintype "passive"))
      (node (ref "D12") (pin "C") (pinfunction "C_C") (pintype "passive"))
      (node (ref "D28") (pin "C") (pinfunction "C_C") (pintype "passive"))
      (node (ref "D29") (pin "C") (pinfunction "C_C") (pintype "passive"))
      (node (ref "D30") (pin "C") (pinfunction "C_C") (pintype "passive"))
      (node (ref "D43") (pin "C") (pinfunction "C_C") (pintype "passive"))
      (node (ref "D44") (pin "C") (pinfunction "C_C") (pintype "passive"))
      (node (ref "JP22") (pin "1") (pinfunction "1_1") (pintype "passive"))
    )
    (net (code "13") (name "Net-(D11-PadA)") (class "Default")
      (node (ref "D11") (pin "A") (pinfunction "A_A") (pintype "passive"))
      (node (ref "S16") (pin "S1") (pinfunction "S1_S1") (pintype "passive"))
    )
    (net (code "14") (name "Net-(D12-PadA)") (class "Default")
      (node (ref "D12") (pin "A") (pinfunction "A_A") (pintype "passive"))
      (node (ref "S4") (pin "S1") (pinfunction "S1_S1") (pintype "passive"))
    )
    (net (code "15") (name "Net-(D13-PadA)") (class "Default")
      (node (ref "D13") (pin "A") (pinfunction "A_A") (pintype "passive"))
      (node (ref "S21") (pin "S1") (pinfunction "S1_S1") (pintype "passive"))
    )
    (net (code "16") (name "Net-(D13-PadC)") (class "Default")
      (node (ref "D13") (pin "C") (pinfunction "C_C") (pintype "passive"))
      (node (ref "D14") (pin "C") (pinfunction "C_C") (pintype "passive"))
      (node (ref "D15") (pin "C") (pinfunction "C_C") (pintype "passive"))
      (node (ref "D31") (pin "C") (pinfunction "C_C") (pintype "passive"))
      (node (ref "D32") (pin "C") (pinfunction "C_C") (pintype "passive"))
      (node (ref "D33") (pin "C") (pinfunction "C_C") (pintype "passive"))
      (node (ref "D45") (pin "C") (pinfunction "C_C") (pintype "passive"))
      (node (ref "D46") (pin "C") (pinfunction "C_C") (pintype "passive"))
      (node (ref "JP24") (pin "1") (pinfunction "1_1") (pintype "passive"))
    )
    (net (code "17") (name "Net-(D14-PadA)") (class "Default")
      (node (ref "D14") (pin "A") (pinfunction "A_A") (pintype "passive"))
      (node (ref "S20") (pin "S1") (pinfunction "S1_S1") (pintype "passive"))
    )
    (net (code "18") (name "Net-(D15-PadA)") (class "Default")
      (node (ref "D15") (pin "A") (pinfunction "A_A") (pintype "passive"))
      (node (ref "S18") (pin "S1") (pinfunction "S1_S1") (pintype "passive"))
    )
    (net (code "19") (name "Net-(D16-PadA)") (class "Default")
      (node (ref "D16") (pin "A") (pinfunction "A_A") (pintype "passive"))
      (node (ref "S23") (pin "S1") (pinfunction "S1_S1") (pintype "passive"))
    )
    (net (code "20") (name "Net-(D16-PadC)") (class "Default")
      (node (ref "D16") (pin "C") (pinfunction "C_C") (pintype "passive"))
      (node (ref "D17") (pin "C") (pinfunction "C_C") (pintype "passive"))
      (node (ref "D18") (pin "C") (pinfunction "C_C") (pintype "passive"))
      (node (ref "D34") (pin "C") (pinfunction "C_C") (pintype "passive"))
      (node (ref "D35") (pin "C") (pinfunction "C_C") (pintype "passive"))
      (node (ref "D36") (pin "C") (pinfunction "C_C") (pintype "passive"))
      (node (ref "D47") (pin "C") (pinfunction "C_C") (pintype "passive"))
      (node (ref "D48") (pin "C") (pinfunction "C_C") (pintype "passive"))
      (node (ref "JP26") (pin "1") (pinfunction "1_1") (pintype "passive"))
    )
    (net (code "21") (name "Net-(D17-PadA)") (class "Default")
      (node (ref "D17") (pin "A") (pinfunction "A_A") (pintype "passive"))
      (node (ref "S22") (pin "S1") (pinfunction "S1_S1") (pintype "passive"))
    )
    (net (code "22") (name "Net-(D18-PadA)") (class "Default")
      (node (ref "D18") (pin "A") (pinfunction "A_A") (pintype "passive"))
      (node (ref "S19") (pin "S1") (pinfunction "S1_S1") (pintype "passive"))
    )
    (net (code "23") (name "Net-(D19-PadA)") (class "Default")
      (node (ref "D19") (pin "A") (pinfunction "A_A") (pintype "passive"))
      (node (ref "S12") (pin "S1") (pinfunction "S1_S1") (pintype "passive"))
    )
    (net (code "24") (name "Net-(D20-PadA)") (class "Default")
      (node (ref "D20") (pin "A") (pinfunction "A_A") (pintype "passive"))
      (node (ref "S11") (pin "S1") (pinfunction "S1_S1") (pintype "passive"))
    )
    (net (code "25") (name "Net-(D21-PadA)") (class "Default")
      (node (ref "D21") (pin "A") (pinfunction "A_A") (pintype "passive"))
      (node (ref "S9") (pin "S1") (pinfunction "S1_S1") (pintype "passive"))
    )
    (net (code "26") (name "Net-(D22-PadA)") (class "Default")
      (node (ref "D22") (pin "A") (pinfunction "A_A") (pintype "passive"))
      (node (ref "S24") (pin "S1") (pinfunction "S1_S1") (pintype "passive"))
    )
    (net (code "27") (name "Net-(D22-PadC)") (class "Default")
      (node (ref "D22") (pin "C") (pinfunction "C_C") (pintype "passive"))
      (node (ref "D23") (pin "C") (pinfunction "C_C") (pintype "passive"))
      (node (ref "D24") (pin "C") (pinfunction "C_C") (pintype "passive"))
      (node (ref "D39") (pin "C") (pinfunction "C_C") (pintype "passive"))
      (node (ref "D4") (pin "C") (pinfunction "C_C") (pintype "passive"))
      (node (ref "D40") (pin "C") (pinfunction "C_C") (pintype "passive"))
      (node (ref "D5") (pin "C") (pinfunction "C_C") (pintype "passive"))
      (node (ref "D6") (pin "C") (pinfunction "C_C") (pintype "passive"))
      (node (ref "JP18") (pin "1") (pinfunction "1_1") (pintype "passive"))
    )
    (net (code "28") (name "Net-(D23-PadA)") (class "Default")
      (node (ref "D23") (pin "A") (pinfunction "A_A") (pintype "passive"))
      (node (ref "S13") (pin "S1") (pinfunction "S1_S1") (pintype "passive"))
    )
    (net (code "29") (name "Net-(D24-PadA)") (class "Default")
      (node (ref "D24") (pin "A") (pinfunction "A_A") (pintype "passive"))
      (node (ref "S10") (pin "S1") (pinfunction "S1_S1") (pintype "passive"))
    )
    (net (code "30") (name "Net-(D25-PadA)") (class "Default")
      (node (ref "D25") (pin "A") (pinfunction "A_A") (pintype "passive"))
      (node (ref "S28") (pin "S1") (pinfunction "S1_S1") (pintype "passive"))
    )
    (net (code "31") (name "Net-(D25-PadC)") (class "Default")
      (node (ref "D25") (pin "C") (pinfunction "C_C") (pintype "passive"))
      (node (ref "D26") (pin "C") (pinfunction "C_C") (pintype "passive"))
      (node (ref "D27") (pin "C") (pinfunction "C_C") (pintype "passive"))
      (node (ref "D41") (pin "C") (pinfunction "C_C") (pintype "passive"))
      (node (ref "D42") (pin "C") (pinfunction "C_C") (pintype "passive"))
      (node (ref "D7") (pin "C") (pinfunction "C_C") (pintype "passive"))
      (node (ref "D8") (pin "C") (pinfunction "C_C") (pintype "passive"))
      (node (ref "D9") (pin "C") (pinfunction "C_C") (pintype "passive"))
      (node (ref "JP20") (pin "1") (pinfunction "1_1") (pintype "passive"))
    )
    (net (code "32") (name "Net-(D26-PadA)") (class "Default")
      (node (ref "D26") (pin "A") (pinfunction "A_A") (pintype "passive"))
      (node (ref "S27") (pin "S1") (pinfunction "S1_S1") (pintype "passive"))
    )
    (net (code "33") (name "Net-(D27-PadA)") (class "Default")
      (node (ref "D27") (pin "A") (pinfunction "A_A") (pintype "passive"))
      (node (ref "S25") (pin "S1") (pinfunction "S1_S1") (pintype "passive"))
    )
    (net (code "34") (name "Net-(D28-PadA)") (class "Default")
      (node (ref "D28") (pin "A") (pinfunction "A_A") (pintype "passive"))
      (node (ref "S30") (pin "S1") (pinfunction "S1_S1") (pintype "passive"))
    )
    (net (code "35") (name "Net-(D29-PadA)") (class "Default")
      (node (ref "D29") (pin "A") (pinfunction "A_A") (pintype "passive"))
      (node (ref "S29") (pin "S1") (pinfunction "S1_S1") (pintype "passive"))
    )
    (net (code "36") (name "Net-(D30-PadA)") (class "Default")
      (node (ref "D30") (pin "A") (pinfunction "A_A") (pintype "passive"))
      (node (ref "S26") (pin "S1") (pinfunction "S1_S1") (pintype "passive"))
    )
    (net (code "37") (name "Net-(D31-PadA)") (class "Default")
      (node (ref "D31") (pin "A") (pinfunction "A_A") (pintype "passive"))
      (node (ref "S34") (pin "S1") (pinfunction "S1_S1") (pintype "passive"))
    )
    (net (code "38") (name "Net-(D32-PadA)") (class "Default")
      (node (ref "D32") (pin "A") (pinfunction "A_A") (pintype "passive"))
      (node (ref "S33") (pin "S1") (pinfunction "S1_S1") (pintype "passive"))
    )
    (net (code "39") (name "Net-(D33-PadA)") (class "Default")
      (node (ref "D33") (pin "A") (pinfunction "A_A") (pintype "passive"))
      (node (ref "S31") (pin "S1") (pinfunction "S1_S1") (pintype "passive"))
    )
    (net (code "40") (name "Net-(D34-PadA)") (class "Default")
      (node (ref "D34") (pin "A") (pinfunction "A_A") (pintype "passive"))
      (node (ref "S36") (pin "S1") (pinfunction "S1_S1") (pintype "passive"))
    )
    (net (code "41") (name "Net-(D35-PadA)") (class "Default")
      (node (ref "D35") (pin "A") (pinfunction "A_A") (pintype "passive"))
      (node (ref "S35") (pin "S1") (pinfunction "S1_S1") (pintype "passive"))
    )
    (net (code "42") (name "Net-(D36-PadA)") (class "Default")
      (node (ref "D36") (pin "A") (pinfunction "A_A") (pintype "passive"))
      (node (ref "S32") (pin "S1") (pinfunction "S1_S1") (pintype "passive"))
    )
    (net (code "43") (name "Net-(D37-PadA)") (class "Default")
      (node (ref "D37") (pin "A") (pinfunction "A_A") (pintype "passive"))
      (node (ref "S38") (pin "S1") (pinfunction "S1_S1") (pintype "passive"))
    )
    (net (code "44") (name "Net-(D38-PadA)") (class "Default")
      (node (ref "D38") (pin "A") (pinfunction "A_A") (pintype "passive"))
      (node (ref "S37") (pin "S1") (pinfunction "S1_S1") (pintype "passive"))
    )
    (net (code "45") (name "Net-(D39-PadA)") (class "Default")
      (node (ref "D39") (pin "A") (pinfunction "A_A") (pintype "passive"))
      (node (ref "S40") (pin "S1") (pinfunction "S1_S1") (pintype "passive"))
    )
    (net (code "46") (name "Net-(D40-PadA)") (class "Default")
      (node (ref "D40") (pin "A") (pinfunction "A_A") (pintype "passive"))
      (node (ref "S39") (pin "S1") (pinfunction "S1_S1") (pintype "passive"))
    )
    (net (code "47") (name "Net-(D41-PadA)") (class "Default")
      (node (ref "D41") (pin "A") (pinfunction "A_A") (pintype "passive"))
      (node (ref "S42") (pin "S1") (pinfunction "S1_S1") (pintype "passive"))
    )
    (net (code "48") (name "Net-(D42-PadA)") (class "Default")
      (node (ref "D42") (pin "A") (pinfunction "A_A") (pintype "passive"))
      (node (ref "S41") (pin "S1") (pinfunction "S1_S1") (pintype "passive"))
    )
    (net (code "49") (name "Net-(D43-PadA)") (class "Default")
      (node (ref "D43") (pin "A") (pinfunction "A_A") (pintype "passive"))
      (node (ref "S44") (pin "S1") (pinfunction "S1_S1") (pintype "passive"))
    )
    (net (code "50") (name "Net-(D44-PadA)") (class "Default")
      (node (ref "D44") (pin "A") (pinfunction "A_A") (pintype "passive"))
      (node (ref "S43") (pin "S1") (pinfunction "S1_S1") (pintype "passive"))
    )
    (net (code "51") (name "Net-(D45-PadA)") (class "Default")
      (node (ref "D45") (pin "A") (pinfunction "A_A") (pintype "passive"))
      (node (ref "S46") (pin "S1") (pinfunction "S1_S1") (pintype "passive"))
    )
    (net (code "52") (name "Net-(D46-PadA)") (class "Default")
      (node (ref "D46") (pin "A") (pinfunction "A_A") (pintype "passive"))
      (node (ref "S45") (pin "S1") (pinfunction "S1_S1") (pintype "passive"))
    )
    (net (code "53") (name "Net-(D47-PadA)") (class "Default")
      (node (ref "D47") (pin "A") (pinfunction "A_A") (pintype "passive"))
      (node (ref "S48") (pin "S1") (pinfunction "S1_S1") (pintype "passive"))
    )
    (net (code "54") (name "Net-(D48-PadA)") (class "Default")
      (node (ref "D48") (pin "A") (pinfunction "A_A") (pintype "passive"))
      (node (ref "S47") (pin "S1") (pinfunction "S1_S1") (pintype "passive"))
    )
    (net (code "55") (name "Net-(JP1-Pad1)") (class "Default")
      (node (ref "JP1") (pin "1") (pinfunction "1_1") (pintype "passive"))
      (node (ref "JP28") (pin "1") (pinfunction "1_1") (pintype "passive"))
      (node (ref "S38") (pin "A") (pinfunction "A_A") (pintype "passive"))
      (node (ref "S40") (pin "A") (pinfunction "A_A") (pintype "passive"))
      (node (ref "S42") (pin "A") (pinfunction "A_A") (pintype "passive"))
      (node (ref "S44") (pin "A") (pinfunction "A_A") (pintype "passive"))
      (node (ref "S46") (pin "A") (pinfunction "A_A") (pintype "passive"))
      (node (ref "S48") (pin "A") (pinfunction "A_A") (pintype "passive"))
    )
    (net (code "56") (name "Net-(JP2-Pad1)") (class "Default")
      (node (ref "JP2") (pin "1") (pinfunction "1_1") (pintype "passive"))
      (node (ref "JP29") (pin "1") (pinfunction "1_1") (pintype "passive"))
      (node (ref "S37") (pin "S2") (pinfunction "S2_S2") (pintype "passive"))
      (node (ref "S39") (pin "S2") (pinfunction "S2_S2") (pintype "passive"))
      (node (ref "S41") (pin "S2") (pinfunction "S2_S2") (pintype "passive"))
      (node (ref "S43") (pin "S2") (pinfunction "S2_S2") (pintype "passive"))
      (node (ref "S45") (pin "S2") (pinfunction "S2_S2") (pintype "passive"))
      (node (ref "S47") (pin "S2") (pinfunction "S2_S2") (pintype "passive"))
    )
    (net (code "57") (name "Net-(JP3-Pad1)") (class "Default")
      (node (ref "JP3") (pin "1") (pinfunction "1_1") (pintype "passive"))
      (node (ref "JP30") (pin "1") (pinfunction "1_1") (pintype "passive"))
      (node (ref "S37") (pin "A") (pinfunction "A_A") (pintype "passive"))
      (node (ref "S39") (pin "A") (pinfunction "A_A") (pintype "passive"))
      (node (ref "S41") (pin "A") (pinfunction "A_A") (pintype "passive"))
      (node (ref "S43") (pin "A") (pinfunction "A_A") (pintype "passive"))
      (node (ref "S45") (pin "A") (pinfunction "A_A") (pintype "passive"))
      (node (ref "S47") (pin "A") (pinfunction "A_A") (pintype "passive"))
    )
    (net (code "58") (name "Net-(JP10-Pad1)") (class "Default")
      (node (ref "JP10") (pin "1") (pinfunction "1_1") (pintype "passive"))
      (node (ref "JP37") (pin "1") (pinfunction "1_1") (pintype "passive"))
      (node (ref "S15") (pin "S2") (pinfunction "S2_S2") (pintype "passive"))
      (node (ref "S17") (pin "S2") (pinfunction "S2_S2") (pintype "passive"))
      (node (ref "S21") (pin "S2") (pinfunction "S2_S2") (pintype "passive"))
      (node (ref "S23") (pin "S2") (pinfunction "S2_S2") (pintype "passive"))
      (node (ref "S6") (pin "S2") (pinfunction "S2_S2") (pintype "passive"))
      (node (ref "S8") (pin "S2") (pinfunction "S2_S2") (pintype "passive"))
    )
    (net (code "59") (name "Net-(JP11-Pad1)") (class "Default")
      (node (ref "JP11") (pin "1") (pinfunction "1_1") (pintype "passive"))
      (node (ref "JP38") (pin "1") (pinfunction "1_1") (pintype "passive"))
      (node (ref "S15") (pin "A") (pinfunction "A_A") (pintype "passive"))
      (node (ref "S17") (pin "A") (pinfunction "A_A") (pintype "passive"))
      (node (ref "S21") (pin "A") (pinfunction "A_A") (pintype "passive"))
      (node (ref "S23") (pin "A") (pinfunction "A_A") (pintype "passive"))
      (node (ref "S6") (pin "A") (pinfunction "A_A") (pintype "passive"))
      (node (ref "S8") (pin "A") (pinfunction "A_A") (pintype "passive"))
    )
    (net (code "60") (name "Net-(JP12-Pad1)") (class "Default")
      (node (ref "JP12") (pin "1") (pinfunction "1_1") (pintype "passive"))
      (node (ref "JP39") (pin "1") (pinfunction "1_1") (pintype "passive"))
      (node (ref "S14") (pin "S2") (pinfunction "S2_S2") (pintype "passive"))
      (node (ref "S16") (pin "S2") (pinfunction "S2_S2") (pintype "passive"))
      (node (ref "S20") (pin "S2") (pinfunction "S2_S2") (pintype "passive"))
      (node (ref "S22") (pin "S2") (pinfunction "S2_S2") (pintype "passive"))
      (node (ref "S5") (pin "S2") (pinfunction "S2_S2") (pintype "passive"))
      (node (ref "S7") (pin "S2") (pinfunction "S2_S2") (pintype "passive"))
    )
    (net (code "61") (name "Net-(JP13-Pad1)") (class "Default")
      (node (ref "JP13") (pin "1") (pinfunction "1_1") (pintype "passive"))
      (node (ref "JP40") (pin "1") (pinfunction "1_1") (pintype "passive"))
      (node (ref "S14") (pin "A") (pinfunction "A_A") (pintype "passive"))
      (node (ref "S16") (pin "A") (pinfunction "A_A") (pintype "passive"))
      (node (ref "S20") (pin "A") (pinfunction "A_A") (pintype "passive"))
      (node (ref "S22") (pin "A") (pinfunction "A_A") (pintype "passive"))
      (node (ref "S5") (pin "A") (pinfunction "A_A") (pintype "passive"))
      (node (ref "S7") (pin "A") (pinfunction "A_A") (pintype "passive"))
    )
    (net (code "62") (name "Net-(JP14-Pad1)") (class "Default")
      (node (ref "JP14") (pin "1") (pinfunction "1_1") (pintype "passive"))
      (node (ref "JP41") (pin "1") (pinfunction "1_1") (pintype "passive"))
      (node (ref "S1") (pin "S2") (pinfunction "S2_S2") (pintype "passive"))
      (node (ref "S18") (pin "S2") (pinfunction "S2_S2") (pintype "passive"))
      (node (ref "S19") (pin "S2") (pinfunction "S2_S2") (pintype "passive"))
      (node (ref "S2") (pin "S2") (pinfunction "S2_S2") (pintype "passive"))
      (node (ref "S3") (pin "S2") (pinfunction "S2_S2") (pintype "passive"))
      (node (ref "S4") (pin "S2") (pinfunction "S2_S2") (pintype "passive"))
    )
    (net (code "63") (name "Net-(JP15-Pad1)") (class "Default")
      (node (ref "JP15") (pin "1") (pinfunction "1_1") (pintype "passive"))
      (node (ref "JP42") (pin "1") (pinfunction "1_1") (pintype "passive"))
      (node (ref "S1") (pin "A") (pinfunction "A_A") (pintype "passive"))
      (node (ref "S18") (pin "A") (pinfunction "A_A") (pintype "passive"))
      (node (ref "S19") (pin "A") (pinfunction "A_A") (pintype "passive"))
      (node (ref "S2") (pin "A") (pinfunction "A_A") (pintype "passive"))
      (node (ref "S3") (pin "A") (pinfunction "A_A") (pintype "passive"))
      (node (ref "S4") (pin "A") (pinfunction "A_A") (pintype "passive"))
    )
    (net (code "64") (name "Net-(JP16-Pad1)") (class "Default")
      (node (ref "JP16") (pin "1") (pinfunction "1_1") (pintype "passive"))
      (node (ref "JP27") (pin "1") (pinfunction "1_1") (pintype "passive"))
      (node (ref "S38") (pin "S2") (pinfunction "S2_S2") (pintype "passive"))
      (node (ref "S40") (pin "S2") (pinfunction "S2_S2") (pintype "passive"))
      (node (ref "S42") (pin "S2") (pinfunction "S2_S2") (pintype "passive"))
      (node (ref "S44") (pin "S2") (pinfunction "S2_S2") (pintype "passive"))
      (node (ref "S46") (pin "S2") (pinfunction "S2_S2") (pintype "passive"))
      (node (ref "S48") (pin "S2") (pinfunction "S2_S2") (pintype "passive"))
    )
    (net (code "65") (name "Net-(JP31-Pad1)") (class "Default")
      (node (ref "JP31") (pin "1") (pinfunction "1_1") (pintype "passive"))
      (node (ref "JP4") (pin "1") (pinfunction "1_1") (pintype "passive"))
      (node (ref "S12") (pin "S2") (pinfunction "S2_S2") (pintype "passive"))
      (node (ref "S24") (pin "S2") (pinfunction "S2_S2") (pintype "passive"))
      (node (ref "S28") (pin "S2") (pinfunction "S2_S2") (pintype "passive"))
      (node (ref "S30") (pin "S2") (pinfunction "S2_S2") (pintype "passive"))
      (node (ref "S34") (pin "S2") (pinfunction "S2_S2") (pintype "passive"))
      (node (ref "S36") (pin "S2") (pinfunction "S2_S2") (pintype "passive"))
    )
    (net (code "66") (name "Net-(JP32-Pad1)") (class "Default")
      (node (ref "JP32") (pin "1") (pinfunction "1_1") (pintype "passive"))
      (node (ref "JP5") (pin "1") (pinfunction "1_1") (pintype "passive"))
      (node (ref "S12") (pin "A") (pinfunction "A_A") (pintype "passive"))
      (node (ref "S24") (pin "A") (pinfunction "A_A") (pintype "passive"))
      (node (ref "S28") (pin "A") (pinfunction "A_A") (pintype "passive"))
      (node (ref "S30") (pin "A") (pinfunction "A_A") (pintype "passive"))
      (node (ref "S34") (pin "A") (pinfunction "A_A") (pintype "passive"))
      (node (ref "S36") (pin "A") (pinfunction "A_A") (pintype "passive"))
    )
    (net (code "67") (name "Net-(JP33-Pad1)") (class "Default")
      (node (ref "JP33") (pin "1") (pinfunction "1_1") (pintype "passive"))
      (node (ref "JP6") (pin "1") (pinfunction "1_1") (pintype "passive"))
      (node (ref "S11") (pin "S2") (pinfunction "S2_S2") (pintype "passive"))
      (node (ref "S13") (pin "S2") (pinfunction "S2_S2") (pintype "passive"))
      (node (ref "S27") (pin "S2") (pinfunction "S2_S2") (pintype "passive"))
      (node (ref "S29") (pin "S2") (pinfunction "S2_S2") (pintype "passive"))
      (node (ref "S33") (pin "S2") (pinfunction "S2_S2") (pintype "passive"))
      (node (ref "S35") (pin "S2") (pinfunction "S2_S2") (pintype "passive"))
    )
    (net (code "68") (name "Net-(JP34-Pad1)") (class "Default")
      (node (ref "JP34") (pin "1") (pinfunction "1_1") (pintype "passive"))
      (node (ref "JP7") (pin "1") (pinfunction "1_1") (pintype "passive"))
      (node (ref "S11") (pin "A") (pinfunction "A_A") (pintype "passive"))
      (node (ref "S13") (pin "A") (pinfunction "A_A") (pintype "passive"))
      (node (ref "S27") (pin "A") (pinfunction "A_A") (pintype "passive"))
      (node (ref "S29") (pin "A") (pinfunction "A_A") (pintype "passive"))
      (node (ref "S33") (pin "A") (pinfunction "A_A") (pintype "passive"))
      (node (ref "S35") (pin "A") (pinfunction "A_A") (pintype "passive"))
    )
    (net (code "69") (name "Net-(JP35-Pad1)") (class "Default")
      (node (ref "JP35") (pin "1") (pinfunction "1_1") (pintype "passive"))
      (node (ref "JP8") (pin "1") (pinfunction "1_1") (pintype "passive"))
      (node (ref "S10") (pin "S2") (pinfunction "S2_S2") (pintype "passive"))
      (node (ref "S25") (pin "S2") (pinfunction "S2_S2") (pintype "passive"))
      (node (ref "S26") (pin "S2") (pinfunction "S2_S2") (pintype "passive"))
      (node (ref "S31") (pin "S2") (pinfunction "S2_S2") (pintype "passive"))
      (node (ref "S32") (pin "S2") (pinfunction "S2_S2") (pintype "passive"))
      (node (ref "S9") (pin "S2") (pinfunction "S2_S2") (pintype "passive"))
    )
    (net (code "70") (name "Net-(JP36-Pad1)") (class "Default")
      (node (ref "JP36") (pin "1") (pinfunction "1_1") (pintype "passive"))
      (node (ref "JP9") (pin "1") (pinfunction "1_1") (pintype "passive"))
      (node (ref "S10") (pin "A") (pinfunction "A_A") (pintype "passive"))
      (node (ref "S25") (pin "A") (pinfunction "A_A") (pintype "passive"))
      (node (ref "S26") (pin "A") (pinfunction "A_A") (pintype "passive"))
      (node (ref "S31") (pin "A") (pinfunction "A_A") (pintype "passive"))
      (node (ref "S32") (pin "A") (pinfunction "A_A") (pintype "passive"))
      (node (ref "S9") (pin "A") (pinfunction "A_A") (pintype "passive"))
    )
    (net (code "71") (name "Net-(S1-C)") (class "Default")
      (node (ref "JP17") (pin "1") (pinfunction "1_1") (pintype "passive"))
      (node (ref "S1") (pin "K") (pinfunction "C_K") (pintype "passive"))
      (node (ref "S11") (pin "K") (pinfunction "C_K") (pintype "passive"))
      (node (ref "S12") (pin "K") (pinfunction "C_K") (pintype "passive"))
      (node (ref "S37") (pin "K") (pinfunction "C_K") (pintype "passive"))
      (node (ref "S38") (pin "K") (pinfunction "C_K") (pintype "passive"))
      (node (ref "S5") (pin "K") (pinfunction "C_K") (pintype "passive"))
      (node (ref "S6") (pin "K") (pinfunction "C_K") (pintype "passive"))
      (node (ref "S9") (pin "K") (pinfunction "C_K") (pintype "passive"))
    )
    (net (code "72") (name "Net-(S10-C)") (class "Default")
      (node (ref "JP19") (pin "1") (pinfunction "1_1") (pintype "passive"))
      (node (ref "S10") (pin "K") (pinfunction "C_K") (pintype "passive"))
      (node (ref "S13") (pin "K") (pinfunction "C_K") (pintype "passive"))
      (node (ref "S2") (pin "K") (pinfunction "C_K") (pintype "passive"))
      (node (ref "S24") (pin "K") (pinfunction "C_K") (pintype "passive"))
      (node (ref "S39") (pin "K") (pinfunction "C_K") (pintype "passive"))
      (node (ref "S40") (pin "K") (pinfunction "C_K") (pintype "passive"))
      (node (ref "S7") (pin "K") (pinfunction "C_K") (pintype "passive"))
      (node (ref "S8") (pin "K") (pinfunction "C_K") (pintype "passive"))
    )
    (net (code "73") (name "Net-(S14-C)") (class "Default")
      (node (ref "JP21") (pin "1") (pinfunction "1_1") (pintype "passive"))
      (node (ref "S14") (pin "K") (pinfunction "C_K") (pintype "passive"))
      (node (ref "S15") (pin "K") (pinfunction "C_K") (pintype "passive"))
      (node (ref "S25") (pin "K") (pinfunction "C_K") (pintype "passive"))
      (node (ref "S27") (pin "K") (pinfunction "C_K") (pintype "passive"))
      (node (ref "S28") (pin "K") (pinfunction "C_K") (pintype "passive"))
      (node (ref "S3") (pin "K") (pinfunction "C_K") (pintype "passive"))
      (node (ref "S41") (pin "K") (pinfunction "C_K") (pintype "passive"))
      (node (ref "S42") (pin "K") (pinfunction "C_K") (pintype "passive"))
    )
    (net (code "74") (name "Net-(S16-C)") (class "Default")
      (node (ref "JP23") (pin "1") (pinfunction "1_1") (pintype "passive"))
      (node (ref "S16") (pin "K") (pinfunction "C_K") (pintype "passive"))
      (node (ref "S17") (pin "K") (pinfunction "C_K") (pintype "passive"))
      (node (ref "S26") (pin "K") (pinfunction "C_K") (pintype "passive"))
      (node (ref "S29") (pin "K") (pinfunction "C_K") (pintype "passive"))
      (node (ref "S30") (pin "K") (pinfunction "C_K") (pintype "passive"))
      (node (ref "S4") (pin "K") (pinfunction "C_K") (pintype "passive"))
      (node (ref "S43") (pin "K") (pinfunction "C_K") (pintype "passive"))
      (node (ref "S44") (pin "K") (pinfunction "C_K") (pintype "passive"))
    )
    (net (code "75") (name "Net-(S18-C)") (class "Default")
      (node (ref "JP25") (pin "1") (pinfunction "1_1") (pintype "passive"))
      (node (ref "S18") (pin "K") (pinfunction "C_K") (pintype "passive"))
      (node (ref "S20") (pin "K") (pinfunction "C_K") (pintype "passive"))
      (node (ref "S21") (pin "K") (pinfunction "C_K") (pintype "passive"))
      (node (ref "S31") (pin "K") (pinfunction "C_K") (pintype "passive"))
      (node (ref "S33") (pin "K") (pinfunction "C_K") (pintype "passive"))
      (node (ref "S34") (pin "K") (pinfunction "C_K") (pintype "passive"))
      (node (ref "S45") (pin "K") (pinfunction "C_K") (pintype "passive"))
      (node (ref "S46") (pin "K") (pinfunction "C_K") (pintype "passive"))
    )
    (net (code "76") (name "Net-(S19-C)") (class "Default")
      (node (ref "JP44") (pin "1") (pinfunction "1_1") (pintype "passive"))
      (node (ref "S19") (pin "K") (pinfunction "C_K") (pintype "passive"))
      (node (ref "S22") (pin "K") (pinfunction "C_K") (pintype "passive"))
      (node (ref "S23") (pin "K") (pinfunction "C_K") (pintype "passive"))
      (node (ref "S32") (pin "K") (pinfunction "C_K") (pintype "passive"))
      (node (ref "S35") (pin "K") (pinfunction "C_K") (pintype "passive"))
      (node (ref "S36") (pin "K") (pinfunction "C_K") (pintype "passive"))
      (node (ref "S47") (pin "K") (pinfunction "C_K") (pintype "passive"))
      (node (ref "S48") (pin "K") (pinfunction "C_K") (pintype "passive"))
    )
    (net (code "77") (name "unconnected-(J1-1-PadP$1)") (class "Default")
      (node (ref "J1") (pin "P$1") (pinfunction "1_P$1") (pintype "passive"))
    )
    (net (code "78") (name "unconnected-(J2-1-PadP$1)") (class "Default")
      (node (ref "J2") (pin "P$1") (pinfunction "1_P$1") (pintype "passive"))
    )
    (net (code "79") (name "unconnected-(J3-1-PadP$1)") (class "Default")
      (node (ref "J3") (pin "P$1") (pinfunction "1_P$1") (pintype "passive"))
    )
    (net (code "80") (name "unconnected-(J4-1-PadP$1)") (class "Default")
      (node (ref "J4") (pin "P$1") (pinfunction "1_P$1") (pintype "passive"))
    )
    (net (code "81") (name "unconnected-(J5-1-PadP$1)") (class "Default")
      (node (ref "J5") (pin "P$1") (pinfunction "1_P$1") (pintype "passive"))
    )
  )
)
